# Sensor_ExpandBoard_BH1750FV.net
KiCad netlist of a schematic drawn in Altium Designer
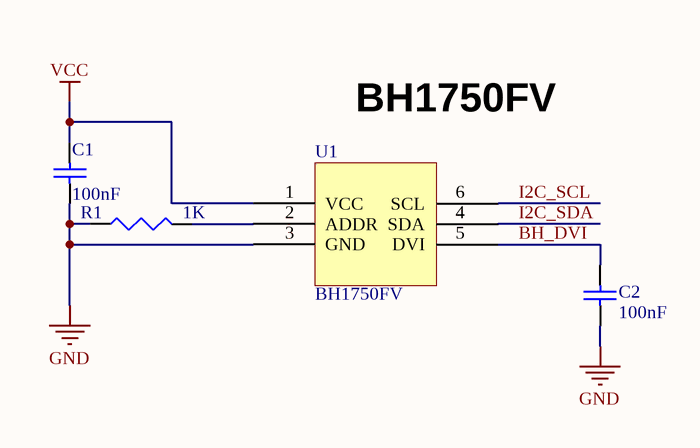
[diagram p0: Sensor_ExpandBoard_BH1750FV.SchDoc]

(export (version "E")
  (design (tool "Eeschema 10.0.6"))
  (components
    (comp (ref "C1")
      (value "100nF")
      (footprint "0603-2")
      (description "无极性电容")
      (fields (field (name "PUBLISHER") "Altium Limited"))
      (libsource (lib "Fszhang") (part "Cap"))
    )
    (comp (ref "C2")
      (value "100nF")
      (footprint "0603-2")
      (description "无极性电容")
      (fields (field (name "PUBLISHER") "Altium Limited"))
      (libsource (lib "Fszhang") (part "Cap"))
    )
    (comp (ref "R1")
      (value "1K")
      (footprint "R0603")
      (description "Resistor")
      (fields (field (name "PUBLISHER") "Altium Limited"))
      (libsource (lib "step") (part "Res"))
    )
    (comp (ref "U1")
      (value "BH1750FV")
      (footprint "WSOF6")
      (description "环境光传感器")
      (libsource (lib "Sensor") (part "BH1750"))
    )
  )
  (nets
    (net (code "1") (name "/BH_DVI") (class "Default")
      (node (ref "C2") (pin "1") (pinfunction "1_1") (pintype "passive"))
      (node (ref "U1") (pin "5") (pinfunction "DVI_5") (pintype "passive"))
    )
    (net (code "2") (name "/I2C_SCL") (class "Default")
      (node (ref "U1") (pin "6") (pinfunction "SCL_6") (pintype "passive"))
    )
    (net (code "3") (name "/I2C_SDA") (class "Default")
      (node (ref "U1") (pin "4") (pinfunction "SDA_4") (pintype "passive"))
    )
    (net (code "4") (name "GND") (class "Default")
      (node (ref "C1") (pin "2") (pinfunction "2_2") (pintype "passive"))
      (node (ref "C2") (pin "2") (pinfunction "2_2") (pintype "passive"))
      (node (ref "R1") (pin "1") (pinfunction "1_1") (pintype "passive"))
      (node (ref "U1") (pin "3") (pinfunction "GND_3") (pintype "passive"))
    )
    (net (code "5") (name "Net-(U1-ADDR)") (class "Default")
      (node (ref "R1") (pin "2") (pinfunction "2_2") (pintype "passive"))
      (node (ref "U1") (pin "2") (pinfunction "ADDR_2") (pintype "passive"))
    )
    (net (code "6") (name "VCC") (class "Default")
      (node (ref "C1") (pin "1") (pinfunction "1_1") (pintype "passive"))
      (node (ref "U1") (pin "1") (pinfunction "VCC_1") (pintype "passive"))
    )
  )
)
